# schema.net
KiCad netlist of a schematic drawn in EAGLE
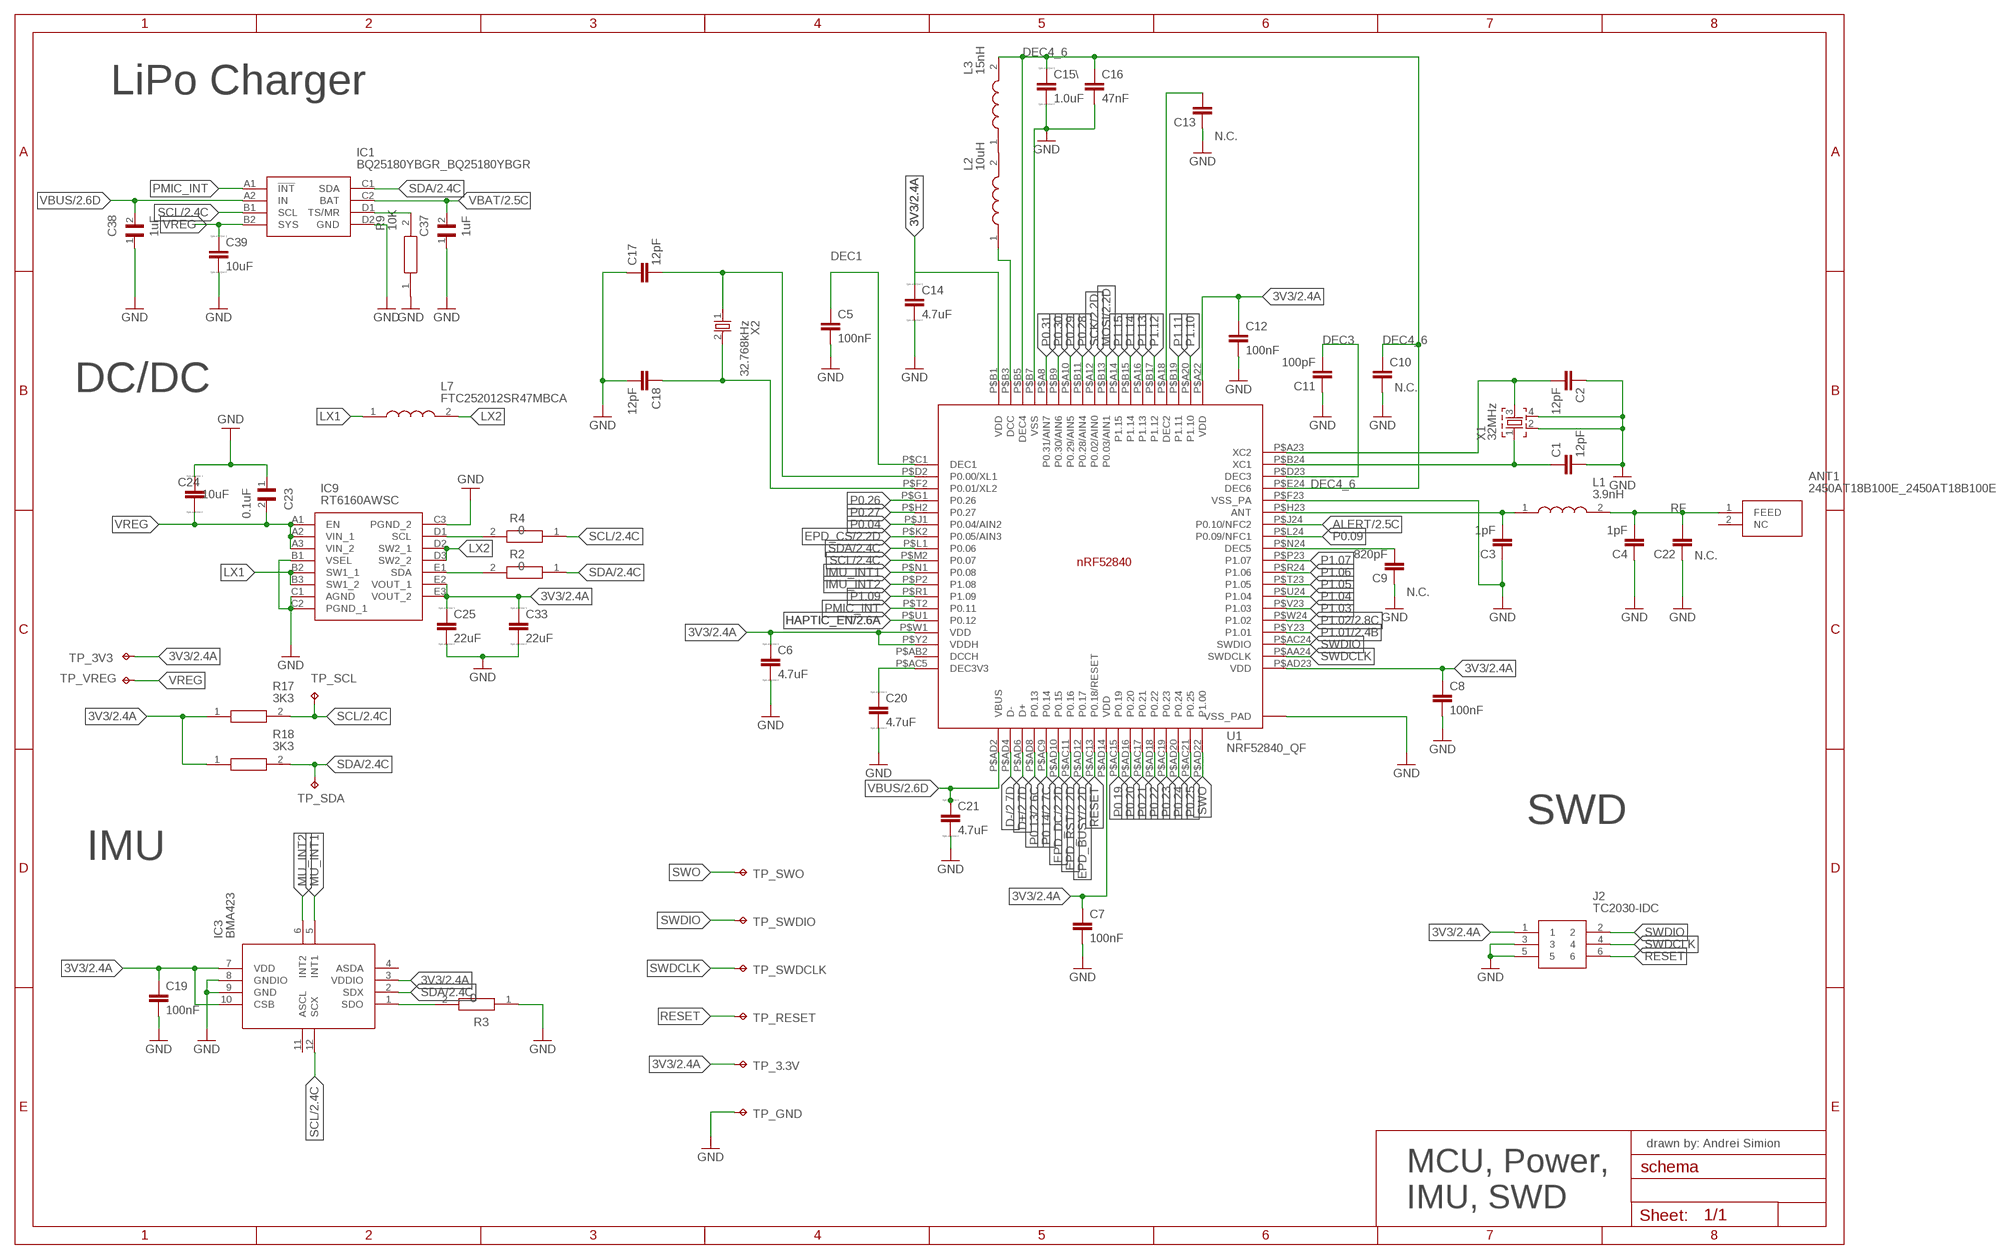
[diagram p0: schematic, sheet 1, part 1 of 2]
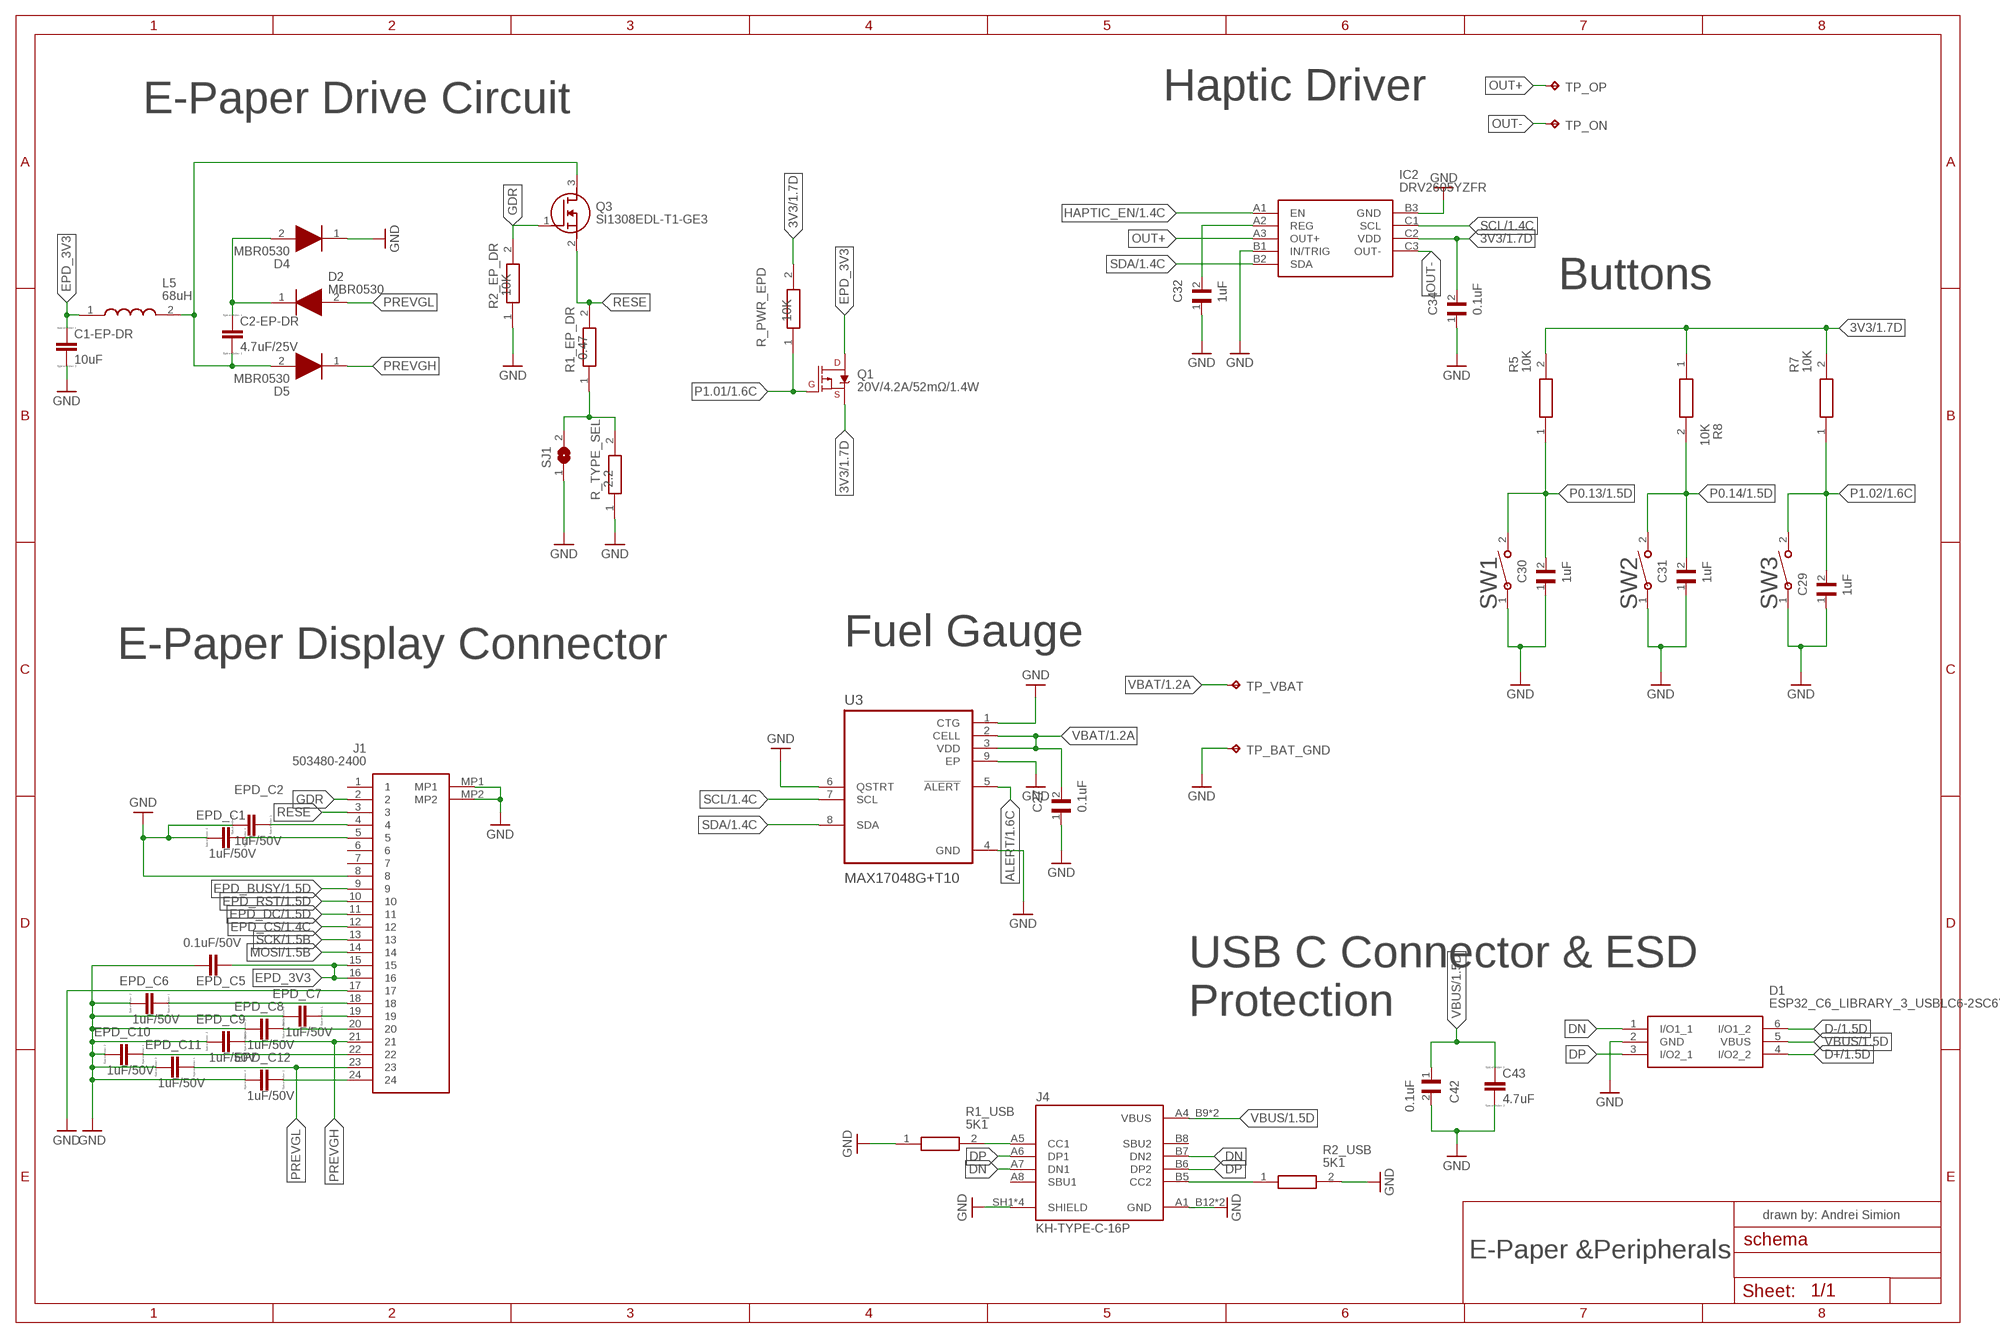
[diagram p1: schematic, sheet 1, part 2 of 2]

(export (version "E")
  (design (tool "Eeschema 10.0.6"))
  (components
    (comp (ref "ANT1")
      (value "2450AT18B100E_2450AT18B100E")
      (footprint "eagle-import:2450AT18B100E_ANTC3216X140N")
      (fields
        (field (name "ARROW_PART_NUMBER") "2450AT18B100E")
        (field (name "MOUSER_PART_NUMBER") "609-2450AT18B100E")
      )
      (libsource (lib "eagle-import") (part "2450AT18B100E_2450AT18B100E"))
    )
    (comp (ref "C1")
      (value "12pF")
      (footprint "eagle-import:NORDIC_NRF_3_RESC0201_L")
      (libsource (lib "eagle-import") (part "NORDIC_NRF_3_CAPACITOR_0201_L"))
    )
    (comp (ref "C1-EP-DR")
      (value "10uF")
      (footprint "eagle-import:ESP32_C6_LIBRARY_1_ESP32_WROVER_EAGLE-LTSPICE_C0402")
      (libsource (lib "eagle-import") (part "ESP32_C6_LIBRARY_1_ESP32_WROVER_EAGLE-LTSPICE_CC0402"))
    )
    (comp (ref "C2")
      (value "12pF")
      (footprint "eagle-import:NORDIC_NRF_3_RESC0201_L")
      (libsource (lib "eagle-import") (part "NORDIC_NRF_3_CAPACITOR_0201_L"))
    )
    (comp (ref "C2-EP-DR")
      (value "4.7uF/25V")
      (footprint "eagle-import:ESP32_C6_LIBRARY_1_ESP32_WROVER_EAGLE-LTSPICE_C0402")
      (libsource (lib "eagle-import") (part "ESP32_C6_LIBRARY_1_ESP32_WROVER_EAGLE-LTSPICE_CC0402"))
    )
    (comp (ref "C3")
      (value "1pF")
      (footprint "eagle-import:NORDIC_NRF_3_RESC0201_L")
      (libsource (lib "eagle-import") (part "NORDIC_NRF_3_CAPACITOR_0201_L"))
    )
    (comp (ref "C4")
      (value "1pF")
      (footprint "eagle-import:NORDIC_NRF_3_RESC0201_L")
      (libsource (lib "eagle-import") (part "NORDIC_NRF_3_CAPACITOR_0201_L"))
    )
    (comp (ref "C5")
      (value "100nF")
      (footprint "eagle-import:NORDIC_NRF_3_RESC0201_L")
      (libsource (lib "eagle-import") (part "NORDIC_NRF_3_CAPACITOR_0201_L"))
    )
    (comp (ref "C6")
      (value "4.7uF")
      (footprint "eagle-import:ESP32_C6_LIBRARY_1_ESP32_WROVER_EAGLE-LTSPICE_C0402")
      (libsource (lib "eagle-import") (part "ESP32_C6_LIBRARY_1_ESP32_WROVER_EAGLE-LTSPICE_CC0402"))
    )
    (comp (ref "C7")
      (value "100nF")
      (footprint "eagle-import:NORDIC_NRF_3_RESC0201_L")
      (libsource (lib "eagle-import") (part "NORDIC_NRF_3_CAPACITOR_0201_L"))
    )
    (comp (ref "C8")
      (value "100nF")
      (footprint "eagle-import:NORDIC_NRF_3_RESC0201_L")
      (libsource (lib "eagle-import") (part "NORDIC_NRF_3_CAPACITOR_0201_L"))
    )
    (comp (ref "C9")
      (value "820pF")
      (footprint "eagle-import:NORDIC_NRF_3_RESC0201_L")
      (libsource (lib "eagle-import") (part "NORDIC_NRF_3_CAPACITOR_0201_L"))
    )
    (comp (ref "C10")
      (value "NORDIC_NRF_3_CAPACITOR_0201_L")
      (footprint "eagle-import:NORDIC_NRF_3_RESC0201_L")
      (libsource (lib "eagle-import") (part "NORDIC_NRF_3_CAPACITOR_0201_L"))
    )
    (comp (ref "C11")
      (value "100pF")
      (footprint "eagle-import:NORDIC_NRF_3_RESC0201_L")
      (libsource (lib "eagle-import") (part "NORDIC_NRF_3_CAPACITOR_0201_L"))
    )
    (comp (ref "C12")
      (value "100nF")
      (footprint "eagle-import:NORDIC_NRF_3_RESC0201_L")
      (libsource (lib "eagle-import") (part "NORDIC_NRF_3_CAPACITOR_0201_L"))
    )
    (comp (ref "C13")
      (value "NORDIC_NRF_3_CAPACITOR_0201_L")
      (footprint "eagle-import:NORDIC_NRF_3_RESC0201_L")
      (libsource (lib "eagle-import") (part "NORDIC_NRF_3_CAPACITOR_0201_L"))
    )
    (comp (ref "C14")
      (value "4.7uF")
      (footprint "eagle-import:ESP32_C6_LIBRARY_1_ESP32_WROVER_EAGLE-LTSPICE_C0402")
      (libsource (lib "eagle-import") (part "ESP32_C6_LIBRARY_1_ESP32_WROVER_EAGLE-LTSPICE_CC0402"))
    )
    (comp (ref "C15\\")
      (value "1.0uF")
      (footprint "eagle-import:ESP32_C6_LIBRARY_1_ESP32_WROVER_EAGLE-LTSPICE_C0402")
      (libsource (lib "eagle-import") (part "ESP32_C6_LIBRARY_1_ESP32_WROVER_EAGLE-LTSPICE_CC0402"))
    )
    (comp (ref "C16")
      (value "47nF")
      (footprint "eagle-import:NORDIC_NRF_3_RESC0201_L")
      (libsource (lib "eagle-import") (part "NORDIC_NRF_3_CAPACITOR_0201_L"))
    )
    (comp (ref "C17")
      (value "12pF")
      (footprint "eagle-import:NORDIC_NRF_3_RESC0201_L")
      (libsource (lib "eagle-import") (part "NORDIC_NRF_3_CAPACITOR_0201_L"))
    )
    (comp (ref "C18")
      (value "12pF")
      (footprint "eagle-import:NORDIC_NRF_3_RESC0201_L")
      (libsource (lib "eagle-import") (part "NORDIC_NRF_3_CAPACITOR_0201_L"))
    )
    (comp (ref "C19")
      (value "100nF")
      (footprint "eagle-import:NORDIC_NRF_3_RESC0201_L")
      (libsource (lib "eagle-import") (part "NORDIC_NRF_3_CAPACITOR_0201_L"))
    )
    (comp (ref "C20")
      (value "4.7uF")
      (footprint "eagle-import:ESP32_C6_LIBRARY_1_ESP32_WROVER_EAGLE-LTSPICE_C0402")
      (libsource (lib "eagle-import") (part "ESP32_C6_LIBRARY_1_ESP32_WROVER_EAGLE-LTSPICE_CC0402"))
    )
    (comp (ref "C21")
      (value "4.7uF")
      (footprint "eagle-import:ESP32_C6_LIBRARY_1_ESP32_WROVER_EAGLE-LTSPICE_C0402")
      (libsource (lib "eagle-import") (part "ESP32_C6_LIBRARY_1_ESP32_WROVER_EAGLE-LTSPICE_CC0402"))
    )
    (comp (ref "C22")
      (value "NORDIC_NRF_3_CAPACITOR_0201_L")
      (footprint "eagle-import:NORDIC_NRF_3_RESC0201_L")
      (libsource (lib "eagle-import") (part "NORDIC_NRF_3_CAPACITOR_0201_L"))
    )
    (comp (ref "C23")
      (value "0.1uF")
      (footprint "eagle-import:GRM011R60J152KE01L_2_CAPC0201X13N")
      (fields (field (name "MF") "Murata") (field (name "MP") "GRM011R60J152KE01L"))
      (libsource (lib "eagle-import") (part "GRM011R60J152KE01L_2_GRM011R60J152KE01L"))
    )
    (comp (ref "C24")
      (value "10uF")
      (footprint "eagle-import:ESP32_C6_LIBRARY_1_ESP32_WROVER_EAGLE-LTSPICE_C0402")
      (libsource (lib "eagle-import") (part "ESP32_C6_LIBRARY_1_ESP32_WROVER_EAGLE-LTSPICE_CC0402"))
    )
    (comp (ref "C25")
      (value "22uF")
      (footprint "eagle-import:ESP32_C6_LIBRARY_1_ESP32_WROVER_EAGLE-LTSPICE_C0402")
      (libsource (lib "eagle-import") (part "ESP32_C6_LIBRARY_1_ESP32_WROVER_EAGLE-LTSPICE_CC0402"))
    )
    (comp (ref "C27")
      (value "0.1uF")
      (footprint "eagle-import:GRM011R60J152KE01L_2_CAPC0201X13N")
      (fields (field (name "MF") "Murata") (field (name "MP") "GRM011R60J152KE01L"))
      (libsource (lib "eagle-import") (part "GRM011R60J152KE01L_2_GRM011R60J152KE01L"))
    )
    (comp (ref "C29")
      (value "1uF")
      (footprint "eagle-import:GRM011R60J152KE01L_2_CAPC0201X13N")
      (fields (field (name "MF") "Murata") (field (name "MP") "GRM011R60J152KE01L"))
      (libsource (lib "eagle-import") (part "GRM011R60J152KE01L_2_GRM011R60J152KE01L"))
    )
    (comp (ref "C30")
      (value "1uF")
      (footprint "eagle-import:GRM011R60J152KE01L_2_CAPC0201X13N")
      (fields (field (name "MF") "Murata") (field (name "MP") "GRM011R60J152KE01L"))
      (libsource (lib "eagle-import") (part "GRM011R60J152KE01L_2_GRM011R60J152KE01L"))
    )
    (comp (ref "C31")
      (value "1uF")
      (footprint "eagle-import:GRM011R60J152KE01L_2_CAPC0201X13N")
      (fields (field (name "MF") "Murata") (field (name "MP") "GRM011R60J152KE01L"))
      (libsource (lib "eagle-import") (part "GRM011R60J152KE01L_2_GRM011R60J152KE01L"))
    )
    (comp (ref "C32")
      (value "1uF")
      (footprint "eagle-import:GRM011R60J152KE01L_2_CAPC0201X13N")
      (fields (field (name "MF") "Murata") (field (name "MP") "GRM011R60J152KE01L"))
      (libsource (lib "eagle-import") (part "GRM011R60J152KE01L_2_GRM011R60J152KE01L"))
    )
    (comp (ref "C33")
      (value "22uF")
      (footprint "eagle-import:ESP32_C6_LIBRARY_1_ESP32_WROVER_EAGLE-LTSPICE_C0402")
      (libsource (lib "eagle-import") (part "ESP32_C6_LIBRARY_1_ESP32_WROVER_EAGLE-LTSPICE_CC0402"))
    )
    (comp (ref "C34")
      (value "0.1uF")
      (footprint "eagle-import:GRM011R60J152KE01L_2_CAPC0201X13N")
      (fields (field (name "MF") "Murata") (field (name "MP") "GRM011R60J152KE01L"))
      (libsource (lib "eagle-import") (part "GRM011R60J152KE01L_2_GRM011R60J152KE01L"))
    )
    (comp (ref "C37")
      (value "1uF")
      (footprint "eagle-import:GRM011R60J152KE01L_2_CAPC0201X13N")
      (fields (field (name "MF") "Murata") (field (name "MP") "GRM011R60J152KE01L"))
      (libsource (lib "eagle-import") (part "GRM011R60J152KE01L_2_GRM011R60J152KE01L"))
    )
    (comp (ref "C38")
      (value "1uF")
      (footprint "eagle-import:GRM011R60J152KE01L_2_CAPC0201X13N")
      (fields (field (name "MF") "Murata") (field (name "MP") "GRM011R60J152KE01L"))
      (libsource (lib "eagle-import") (part "GRM011R60J152KE01L_2_GRM011R60J152KE01L"))
    )
    (comp (ref "C39")
      (value "10uF")
      (footprint "eagle-import:ESP32_C6_LIBRARY_1_ESP32_WROVER_EAGLE-LTSPICE_C0402")
      (libsource (lib "eagle-import") (part "ESP32_C6_LIBRARY_1_ESP32_WROVER_EAGLE-LTSPICE_CC0402"))
    )
    (comp (ref "C42")
      (value "0.1uF")
      (footprint "eagle-import:GRM011R60J152KE01L_2_CAPC0201X13N")
      (fields (field (name "MF") "Murata") (field (name "MP") "GRM011R60J152KE01L"))
      (libsource (lib "eagle-import") (part "GRM011R60J152KE01L_2_GRM011R60J152KE01L"))
    )
    (comp (ref "C43")
      (value "4.7uF")
      (footprint "eagle-import:ESP32_C6_LIBRARY_1_ESP32_WROVER_EAGLE-LTSPICE_C0402")
      (libsource (lib "eagle-import") (part "ESP32_C6_LIBRARY_1_ESP32_WROVER_EAGLE-LTSPICE_CC0402"))
    )
    (comp (ref "D1")
      (value "ESP32_C6_LIBRARY_3_USBLC6-2SC6Y")
      (footprint "eagle-import:ESP32_C6_LIBRARY_3_SOT95P280X145-6N")
      (fields (field (name "MF") "STMicroelectronics") (field (name "MP") "USBLC6-2SC6Y"))
      (libsource (lib "eagle-import") (part "ESP32_C6_LIBRARY_3_USBLC6-2SC6Y"))
    )
    (comp (ref "D2")
      (value "MBR0530")
      (footprint "eagle-import:ESP32_C6_LIBRARY_5_SOD3716X135N")
      (fields (field (name "MF") "ON Semiconductor"))
      (libsource (lib "eagle-import") (part "ESP32_C6_LIBRARY_5_MBR0530"))
    )
    (comp (ref "D4")
      (value "MBR0530")
      (footprint "eagle-import:ESP32_C6_LIBRARY_5_SOD3716X135N")
      (fields (field (name "MF") "ON Semiconductor"))
      (libsource (lib "eagle-import") (part "ESP32_C6_LIBRARY_5_MBR0530"))
    )
    (comp (ref "D5")
      (value "MBR0530")
      (footprint "eagle-import:ESP32_C6_LIBRARY_5_SOD3716X135N")
      (fields (field (name "MF") "ON Semiconductor"))
      (libsource (lib "eagle-import") (part "ESP32_C6_LIBRARY_5_MBR0530"))
    )
    (comp (ref "EPD_C1")
      (value "1uF/50V")
      (footprint "eagle-import:ESP32_C6_LIBRARY_1_ESP32_WROVER_EAGLE-LTSPICE_C0402")
      (libsource (lib "eagle-import") (part "ESP32_C6_LIBRARY_1_ESP32_WROVER_EAGLE-LTSPICE_CC0402"))
    )
    (comp (ref "EPD_C2")
      (value "1uF/50V")
      (footprint "eagle-import:ESP32_C6_LIBRARY_1_ESP32_WROVER_EAGLE-LTSPICE_C0402")
      (libsource (lib "eagle-import") (part "ESP32_C6_LIBRARY_1_ESP32_WROVER_EAGLE-LTSPICE_CC0402"))
    )
    (comp (ref "EPD_C5")
      (value "0.1uF/50V")
      (footprint "eagle-import:NORDIC_NRF_3_RESC0201_L")
      (libsource (lib "eagle-import") (part "NORDIC_NRF_3_CAPACITOR_0201_L"))
    )
    (comp (ref "EPD_C6")
      (value "1uF/50V")
      (footprint "eagle-import:ESP32_C6_LIBRARY_1_ESP32_WROVER_EAGLE-LTSPICE_C0402")
      (libsource (lib "eagle-import") (part "ESP32_C6_LIBRARY_1_ESP32_WROVER_EAGLE-LTSPICE_CC0402"))
    )
    (comp (ref "EPD_C7")
      (value "1uF/50V")
      (footprint "eagle-import:ESP32_C6_LIBRARY_1_ESP32_WROVER_EAGLE-LTSPICE_C0402")
      (libsource (lib "eagle-import") (part "ESP32_C6_LIBRARY_1_ESP32_WROVER_EAGLE-LTSPICE_CC0402"))
    )
    (comp (ref "EPD_C8")
      (value "1uF/50V")
      (footprint "eagle-import:ESP32_C6_LIBRARY_1_ESP32_WROVER_EAGLE-LTSPICE_C0402")
      (libsource (lib "eagle-import") (part "ESP32_C6_LIBRARY_1_ESP32_WROVER_EAGLE-LTSPICE_CC0402"))
    )
    (comp (ref "EPD_C9")
      (value "1uF/50V")
      (footprint "eagle-import:ESP32_C6_LIBRARY_1_ESP32_WROVER_EAGLE-LTSPICE_C0402")
      (libsource (lib "eagle-import") (part "ESP32_C6_LIBRARY_1_ESP32_WROVER_EAGLE-LTSPICE_CC0402"))
    )
    (comp (ref "EPD_C10")
      (value "1uF/50V")
      (footprint "eagle-import:ESP32_C6_LIBRARY_1_ESP32_WROVER_EAGLE-LTSPICE_C0402")
      (libsource (lib "eagle-import") (part "ESP32_C6_LIBRARY_1_ESP32_WROVER_EAGLE-LTSPICE_CC0402"))
    )
    (comp (ref "EPD_C11")
      (value "1uF/50V")
      (footprint "eagle-import:ESP32_C6_LIBRARY_1_ESP32_WROVER_EAGLE-LTSPICE_C0402")
      (libsource (lib "eagle-import") (part "ESP32_C6_LIBRARY_1_ESP32_WROVER_EAGLE-LTSPICE_CC0402"))
    )
    (comp (ref "EPD_C12")
      (value "1uF/50V")
      (footprint "eagle-import:ESP32_C6_LIBRARY_1_ESP32_WROVER_EAGLE-LTSPICE_C0402")
      (libsource (lib "eagle-import") (part "ESP32_C6_LIBRARY_1_ESP32_WROVER_EAGLE-LTSPICE_CC0402"))
    )
    (comp (ref "IC1")
      (value "BQ25180YBGR_BQ25180YBGR")
      (footprint "eagle-import:BQ25180YBGR_BGA8C40P2X4_100X155X50")
      (fields
        (field (name "ARROW_PART_NUMBER") "BQ25180YBGR")
        (field (name "MOUSER_PART_NUMBER") "595-BQ25180YBGR")
      )
      (libsource (lib "eagle-import") (part "BQ25180YBGR_BQ25180YBGR"))
    )
    (comp (ref "IC2")
      (value "DRV2605YZFR")
      (footprint "eagle-import:DRV2605YZFR_BGA9C50P3X3_144X144X62")
      (libsource (lib "eagle-import") (part "DRV2605YZFR_DRV2605YZFR"))
    )
    (comp (ref "IC3")
      (value "BMA423")
      (footprint "eagle-import:BMA423_BMA423")
      (fields (field (name "MOUSER_PART_NUMBER") "262-BMA423"))
      (libsource (lib "eagle-import") (part "BMA423_BMA423"))
    )
    (comp (ref "IC9")
      (value "RT6160AWSC")
      (footprint "eagle-import:RT6160AWSC_BGA15C40P3X5_140X230X60")
      (fields (field (name "MOUSER_PART_NUMBER") "835-RT6160AWSC"))
      (libsource (lib "eagle-import") (part "RT6160AWSC_RT6160AWSC"))
    )
    (comp (ref "J1")
      (value "503480-2400")
      (footprint "eagle-import:503480-2400_5034802400")
      (fields (field (name "MOUSER_PART_NUMBER") "538-503480-2400"))
      (libsource (lib "eagle-import") (part "503480-2400_503480-2400"))
    )
    (comp (ref "J2")
      (value "TC2030-IDC")
      (footprint "eagle-import:TC2030-IDC_TC2030IDC")
      (libsource (lib "eagle-import") (part "TC2030-IDC_TC2030-IDC"))
    )
    (comp (ref "J4")
      (value "KH-TYPE-C-16P")
      (footprint "eagle-import:KH-TYPE-C-16P_KINGHELM_KH-TYPE-C-16P")
      (fields (field (name "MF") "kinghelm"))
      (libsource (lib "eagle-import") (part "KH-TYPE-C-16P_KH-TYPE-C-16P"))
    )
    (comp (ref "L1")
      (value "3.9nH")
      (footprint "eagle-import:MLP2016SR47MT0S1_INDC2016X100N")
      (fields (field (name "MANUFACTURER_PART_NUMBER") "FTC252012SR47MBCA"))
      (libsource (lib "eagle-import") (part "MLP2016SR47MT0S1_FTC252012SR47MBCA"))
    )
    (comp (ref "L2")
      (value "10uH")
      (footprint "eagle-import:MLP2016SR47MT0S1_INDC2016X100N")
      (fields (field (name "MANUFACTURER_PART_NUMBER") "FTC252012SR47MBCA"))
      (libsource (lib "eagle-import") (part "MLP2016SR47MT0S1_FTC252012SR47MBCA"))
    )
    (comp (ref "L3")
      (value "15nH")
      (footprint "eagle-import:MLP2016SR47MT0S1_INDC2016X100N")
      (fields (field (name "MANUFACTURER_PART_NUMBER") "FTC252012SR47MBCA"))
      (libsource (lib "eagle-import") (part "MLP2016SR47MT0S1_FTC252012SR47MBCA"))
    )
    (comp (ref "L5")
      (value "68uH")
      (footprint "eagle-import:MLP2016SR47MT0S1_INDC2016X100N")
      (fields (field (name "MANUFACTURER_PART_NUMBER") "FTC252012SR47MBCA"))
      (libsource (lib "eagle-import") (part "MLP2016SR47MT0S1_FTC252012SR47MBCA"))
    )
    (comp (ref "L7")
      (value "FTC252012SR47MBCA")
      (footprint "eagle-import:MLP2016SR47MT0S1_INDC2016X100N")
      (libsource (lib "eagle-import") (part "MLP2016SR47MT0S1_FTC252012SR47MBCA"))
    )
    (comp (ref "Q1")
      (value "20V/4.2A/52mΩ/1.4W")
      (footprint "eagle-import:ESP32_C6_LIBRARY_4_ESP32_C6_LIBRARY_4_ESP32_C6_LIBRARY_4_ESP32_C6_LIBRARY_4_ESP32_WROVER_SPARKFUN-DISCRETESEMI_SOT23-3")
      (libsource (lib "eagle-import") (part "ESP32_C6_LIBRARY_4_ESP32_WROVER_SPARKFUN-DISCRETESEMI_MOSFET_PCH-DMG2305UX-7"))
    )
    (comp (ref "Q3")
      (value "SI1308EDL-T1-GE3")
      (footprint "eagle-import:ESP32_C6_LIBRARY_6_SOT65P210X110-3N")
      (fields (field (name "MF") "Vishay Siliconix"))
      (libsource (lib "eagle-import") (part "ESP32_C6_LIBRARY_6_SI1308EDL-T1-GE3"))
    )
    (comp (ref "R1_EP_DR")
      (value "0.47")
      (footprint "eagle-import:CPF0201D7K68C1_0201")
      (libsource (lib "eagle-import") (part "CPF0201D7K68C1_CPF0201D7K68C1"))
    )
    (comp (ref "R1_USB")
      (value "5K1")
      (footprint "eagle-import:CPF0201D7K68C1_0201")
      (libsource (lib "eagle-import") (part "CPF0201D7K68C1_CPF0201D7K68C1"))
    )
    (comp (ref "R2")
      (value "0")
      (footprint "eagle-import:CPF0201D7K68C1_0201")
      (libsource (lib "eagle-import") (part "CPF0201D7K68C1_CPF0201D7K68C1"))
    )
    (comp (ref "R2_EP_DR")
      (value "10K")
      (footprint "eagle-import:CPF0201D7K68C1_0201")
      (libsource (lib "eagle-import") (part "CPF0201D7K68C1_CPF0201D7K68C1"))
    )
    (comp (ref "R2_USB")
      (value "5K1")
      (footprint "eagle-import:CPF0201D7K68C1_0201")
      (libsource (lib "eagle-import") (part "CPF0201D7K68C1_CPF0201D7K68C1"))
    )
    (comp (ref "R3")
      (value "0")
      (footprint "eagle-import:CPF0201D7K68C1_0201")
      (libsource (lib "eagle-import") (part "CPF0201D7K68C1_CPF0201D7K68C1"))
    )
    (comp (ref "R4")
      (value "0")
      (footprint "eagle-import:CPF0201D7K68C1_0201")
      (libsource (lib "eagle-import") (part "CPF0201D7K68C1_CPF0201D7K68C1"))
    )
    (comp (ref "R5")
      (value "10K")
      (footprint "eagle-import:CPF0201D7K68C1_0201")
      (libsource (lib "eagle-import") (part "CPF0201D7K68C1_CPF0201D7K68C1"))
    )
    (comp (ref "R7")
      (value "10K")
      (footprint "eagle-import:CPF0201D7K68C1_0201")
      (libsource (lib "eagle-import") (part "CPF0201D7K68C1_CPF0201D7K68C1"))
    )
    (comp (ref "R8")
      (value "10K")
      (footprint "eagle-import:CPF0201D7K68C1_0201")
      (libsource (lib "eagle-import") (part "CPF0201D7K68C1_CPF0201D7K68C1"))
    )
    (comp (ref "R9")
      (value "10K")
      (footprint "eagle-import:CPF0201D7K68C1_0201")
      (libsource (lib "eagle-import") (part "CPF0201D7K68C1_CPF0201D7K68C1"))
    )
    (comp (ref "R17")
      (value "3K3")
      (footprint "eagle-import:CPF0201D7K68C1_0201")
      (libsource (lib "eagle-import") (part "CPF0201D7K68C1_CPF0201D7K68C1"))
    )
    (comp (ref "R18")
      (value "3K3")
      (footprint "eagle-import:CPF0201D7K68C1_0201")
      (libsource (lib "eagle-import") (part "CPF0201D7K68C1_CPF0201D7K68C1"))
    )
    (comp (ref "R_PWR_EPD")
      (value "10K")
      (footprint "eagle-import:CPF0201D7K68C1_0201")
      (libsource (lib "eagle-import") (part "CPF0201D7K68C1_CPF0201D7K68C1"))
    )
    (comp (ref "R_TYPE_SEL")
      (value "2.2")
      (footprint "eagle-import:CPF0201D7K68C1_0201")
      (libsource (lib "eagle-import") (part "CPF0201D7K68C1_CPF0201D7K68C1"))
    )
    (comp (ref "SJ1")
      (value "ESP32_C6_LIBRARY_7_JUMPER_SJ")
      (footprint "eagle-import:ESP32_C6_LIBRARY_7_JUMPER_SJ")
      (libsource (lib "eagle-import") (part "ESP32_C6_LIBRARY_7_JUMPER_SJ"))
    )
    (comp (ref "SW1")
      (value "2025-10-22_07-23-44_LIBRARY_EVP-AKE31ASW_EVP-AKE31A_PAN")
      (footprint "eagle-import:2025-10-22_07-23-44_LIBRARY_SW_EVP-AKE31A_PAN")
      (fields
        (field (name "MANUFACTURER_PART_NUMBER") "EVP-AKE31A")
        (field (name "COPYRIGHT") "Copyright (C) 2025 Ultra Librarian. All rights reserved.")
      )
      (libsource (lib "eagle-import") (part "2025-10-22_07-23-44_LIBRARY_EVP-AKE31ASW_EVP-AKE31A_PAN"))
    )
    (comp (ref "SW2")
      (value "2025-10-22_07-23-44_LIBRARY_EVP-AKE31ASW_EVP-AKE31A_PAN")
      (footprint "eagle-import:2025-10-22_07-23-44_LIBRARY_SW_EVP-AKE31A_PAN")
      (fields
        (field (name "MANUFACTURER_PART_NUMBER") "EVP-AKE31A")
        (field (name "COPYRIGHT") "Copyright (C) 2025 Ultra Librarian. All rights reserved.")
      )
      (libsource (lib "eagle-import") (part "2025-10-22_07-23-44_LIBRARY_EVP-AKE31ASW_EVP-AKE31A_PAN"))
    )
    (comp (ref "SW3")
      (value "2025-10-22_07-23-44_LIBRARY_EVP-AKE31ASW_EVP-AKE31A_PAN")
      (footprint "eagle-import:2025-10-22_07-23-44_LIBRARY_SW_EVP-AKE31A_PAN")
      (fields
        (field (name "MANUFACTURER_PART_NUMBER") "EVP-AKE31A")
        (field (name "COPYRIGHT") "Copyright (C) 2025 Ultra Librarian. All rights reserved.")
      )
      (libsource (lib "eagle-import") (part "2025-10-22_07-23-44_LIBRARY_EVP-AKE31ASW_EVP-AKE31A_PAN"))
    )
    (comp (ref "TP_3.3V")
      (value "HECTOR_WATCH_1_TPTP20R")
      (footprint "eagle-import:HECTOR_WATCH_1_TP20R")
      (libsource (lib "eagle-import") (part "HECTOR_WATCH_1_TPTP20R"))
    )
    (comp (ref "TP_3V3")
      (value "HECTOR_WATCH_1_TPTP20R")
      (footprint "eagle-import:HECTOR_WATCH_1_TP20R")
      (libsource (lib "eagle-import") (part "HECTOR_WATCH_1_TPTP20R"))
    )
    (comp (ref "TP_BAT_GND")
      (value "HECTOR_WATCH_1_TPTP20R")
      (footprint "eagle-import:HECTOR_WATCH_1_TP20R")
      (libsource (lib "eagle-import") (part "HECTOR_WATCH_1_TPTP20R"))
    )
    (comp (ref "TP_GND")
      (value "HECTOR_WATCH_1_TPTP20R")
      (footprint "eagle-import:HECTOR_WATCH_1_TP20R")
      (libsource (lib "eagle-import") (part "HECTOR_WATCH_1_TPTP20R"))
    )
    (comp (ref "TP_ON")
      (value "HECTOR_WATCH_1_TPTP20R")
      (footprint "eagle-import:HECTOR_WATCH_1_TP20R")
      (libsource (lib "eagle-import") (part "HECTOR_WATCH_1_TPTP20R"))
    )
    (comp (ref "TP_OP")
      (value "HECTOR_WATCH_1_TPTP20R")
      (footprint "eagle-import:HECTOR_WATCH_1_TP20R")
      (libsource (lib "eagle-import") (part "HECTOR_WATCH_1_TPTP20R"))
    )
    (comp (ref "TP_RESET")
      (value "HECTOR_WATCH_1_TPTP20R")
      (footprint "eagle-import:HECTOR_WATCH_1_TP20R")
      (libsource (lib "eagle-import") (part "HECTOR_WATCH_1_TPTP20R"))
    )
    (comp (ref "TP_SCL")
      (value "HECTOR_WATCH_1_TPTP20R")
      (footprint "eagle-import:HECTOR_WATCH_1_TP20R")
      (libsource (lib "eagle-import") (part "HECTOR_WATCH_1_TPTP20R"))
    )
    (comp (ref "TP_SDA")
      (value "HECTOR_WATCH_1_TPTP20R")
      (footprint "eagle-import:HECTOR_WATCH_1_TP20R")
      (libsource (lib "eagle-import") (part "HECTOR_WATCH_1_TPTP20R"))
    )
    (comp (ref "TP_SWDCLK")
      (value "HECTOR_WATCH_1_TPTP20R")
      (footprint "eagle-import:HECTOR_WATCH_1_TP20R")
      (libsource (lib "eagle-import") (part "HECTOR_WATCH_1_TPTP20R"))
    )
    (comp (ref "TP_SWDIO")
      (value "HECTOR_WATCH_1_TPTP20R")
      (footprint "eagle-import:HECTOR_WATCH_1_TP20R")
      (libsource (lib "eagle-import") (part "HECTOR_WATCH_1_TPTP20R"))
    )
    (comp (ref "TP_SWO")
      (value "HECTOR_WATCH_1_TPTP20R")
      (footprint "eagle-import:HECTOR_WATCH_1_TP20R")
      (libsource (lib "eagle-import") (part "HECTOR_WATCH_1_TPTP20R"))
    )
    (comp (ref "TP_VBAT")
      (value "HECTOR_WATCH_1_TPTP20R")
      (footprint "eagle-import:HECTOR_WATCH_1_TP20R")
      (libsource (lib "eagle-import") (part "HECTOR_WATCH_1_TPTP20R"))
    )
    (comp (ref "TP_VREG")
      (value "HECTOR_WATCH_1_TPTP20R")
      (footprint "eagle-import:HECTOR_WATCH_1_TP20R")
      (libsource (lib "eagle-import") (part "HECTOR_WATCH_1_TPTP20R"))
    )
    (comp (ref "U1")
      (value "NRF52840_QF")
      (footprint "eagle-import:NORDIC_NRF_4_AQFN50P700X700X85_HS-74N")
      (libsource (lib "eagle-import") (part "NORDIC_NRF_4_NRF52840_QF"))
    )
    (comp (ref "U3")
      (value "MAX17048G+T10")
      (footprint "eagle-import:ESP32_C6_LIBRARY_SON50P200X200X80-9N")
      (fields (field (name "MF") "Analog Devices"))
      (libsource (lib "eagle-import") (part "ESP32_C6_LIBRARY_MAX17048G+T10"))
    )
    (comp (ref "X1")
      (value "32MHz")
      (footprint "eagle-import:NORDIC_NRF_BT-XTAL_2016_N")
      (libsource (lib "eagle-import") (part "NORDIC_NRF_XTAL_32MHZ"))
    )
    (comp (ref "X2")
      (value "32.768kHz")
      (footprint "eagle-import:NORDIC_NRF_1_XTAL_3215_N")
      (libsource (lib "eagle-import") (part "NORDIC_NRF_1_XTAL_32KHZ"))
    )
  )
  (nets
    (net (code "1") (name "3V3{slash}1.7D") (class "Default")
      (node (ref "C34") (pin "2") (pinfunction "2_2") (pintype "passive"))
      (node (ref "IC2") (pin "C2") (pinfunction "VDD_C2") (pintype "bidirectional"))
      (node (ref "Q1") (pin "2") (pinfunction "S_2") (pintype "bidirectional"))
      (node (ref "R5") (pin "2") (pinfunction "2_2") (pintype "bidirectional"))
      (node (ref "R7") (pin "2") (pinfunction "2_2") (pintype "bidirectional"))
      (node (ref "R8") (pin "1") (pinfunction "1_1") (pintype "bidirectional"))
      (node (ref "R_PWR_EPD") (pin "2") (pinfunction "2_2") (pintype "bidirectional"))
    )
    (net (code "2") (name "3V3{slash}2.4A") (class "Default")
      (node (ref "C12") (pin "1") (pinfunction "1_1") (pintype "passive"))
      (node (ref "C14") (pin "1") (pinfunction "1_1") (pintype "passive"))
      (node (ref "C19") (pin "1") (pinfunction "1_1") (pintype "passive"))
      (node (ref "C25") (pin "1") (pinfunction "1_1") (pintype "passive"))
      (node (ref "C33") (pin "1") (pinfunction "1_1") (pintype "passive"))
      (node (ref "C6") (pin "1") (pinfunction "1_1") (pintype "passive"))
      (node (ref "C7") (pin "1") (pinfunction "1_1") (pintype "passive"))
      (node (ref "C8") (pin "1") (pinfunction "1_1") (pintype "passive"))
      (node (ref "IC3") (pin "10") (pinfunction "CSB_10") (pintype "bidirectional"))
      (node (ref "IC3") (pin "3") (pinfunction "VDDIO_3") (pintype "bidirectional"))
      (node (ref "IC3") (pin "7") (pinfunction "VDD_7") (pintype "bidirectional"))
      (node (ref "IC9") (pin "E2") (pinfunction "VOUT_1_E2") (pintype "bidirectional"))
      (node (ref "IC9") (pin "E3") (pinfunction "VOUT_2_E3") (pintype "bidirectional"))
      (node (ref "J2") (pin "1") (pinfunction "1_1") (pintype "bidirectional"))
      (node (ref "R17") (pin "1") (pinfunction "1_1") (pintype "bidirectional"))
      (node (ref "R18") (pin "1") (pinfunction "1_1") (pintype "bidirectional"))
      (node (ref "TP_3.3V") (pin "TP") (pinfunction "TP_TP") (pintype "input"))
      (node (ref "TP_3V3") (pin "TP") (pinfunction "TP_TP") (pintype "input"))
      (node (ref "U1") (pin "P$A22") (pinfunction "VDD_P$A22") (pintype "power_in"))
      (node (ref "U1") (pin "P$AD14") (pinfunction "VDD_P$AD14") (pintype "power_in"))
      (node (ref "U1") (pin "P$AD23") (pinfunction "VDD_P$AD23") (pintype "power_in"))
      (node (ref "U1") (pin "P$B1") (pinfunction "VDD_P$B1") (pintype "power_in"))
      (node (ref "U1") (pin "P$W1") (pinfunction "VDD_P$W1") (pintype "power_in"))
      (node (ref "U1") (pin "P$Y2") (pinfunction "VDDH_P$Y2") (pintype "power_in"))
    )
    (net (code "3") (name "ALERT{slash}1.6C") (class "Default")
      (node (ref "U3") (pin "5") (pinfunction "~{ALERT}_5") (pintype "output"))
    )
    (net (code "4") (name "ALERT{slash}2.5C") (class "Default")
      (node (ref "U1") (pin "P$J24") (pinfunction "P0.10/NFC2_P$J24") (pintype "bidirectional"))
    )
    (net (code "5") (name "D+{slash}1.5D") (class "Default")
      (node (ref "D1") (pin "4") (pinfunction "I/O2_2_4") (pintype "bidirectional"))
    )
    (net (code "6") (name "D+{slash}2.7D") (class "Default")
      (node (ref "U1") (pin "P$AD6") (pinfunction "D+_P$AD6") (pintype "bidirectional"))
    )
    (net (code "7") (name "D-{slash}1.5D") (class "Default")
      (node (ref "D1") (pin "6") (pinfunction "I/O1_2_6") (pintype "bidirectional"))
    )
    (net (code "8") (name "D-{slash}2.7D") (class "Default")
      (node (ref "U1") (pin "P$AD4") (pinfunction "D-_P$AD4") (pintype "bidirectional"))
    )
    (net (code "9") (name "DN") (class "Default")
      (node (ref "D1") (pin "1") (pinfunction "I/O1_1_1") (pintype "bidirectional"))
      (node (ref "J4") (pin "A7") (pinfunction "DN1_A7") (pintype "bidirectional"))
      (node (ref "J4") (pin "B7") (pinfunction "DN2_B7") (pintype "bidirectional"))
    )
    (net (code "10") (name "DP") (class "Default")
      (node (ref "D1") (pin "3") (pinfunction "I/O2_1_3") (pintype "bidirectional"))
      (node (ref "J4") (pin "A6") (pinfunction "DP1_A6") (pintype "bidirectional"))
      (node (ref "J4") (pin "B6") (pinfunction "DP2_B6") (pintype "bidirectional"))
    )
    (net (code "11") (name "EPD_3V3") (class "Default")
      (node (ref "C1-EP-DR") (pin "1") (pinfunction "1_1") (pintype "passive"))
      (node (ref "EPD_C5") (pin "1") (pinfunction "1_1") (pintype "passive"))
      (node (ref "J1") (pin "15") (pinfunction "15_15") (pintype "bidirectional"))
      (node (ref "J1") (pin "16") (pinfunction "16_16") (pintype "bidirectional"))
      (node (ref "L5") (pin "1") (pinfunction "1_1") (pintype "bidirectional"))
      (node (ref "Q1") (pin "3") (pinfunction "D_3") (pintype "bidirectional"))
    )
    (net (code "12") (name "EPD_BUSY{slash}1.5D") (class "Default")
      (node (ref "J1") (pin "9") (pinfunction "9_9") (pintype "bidirectional"))
    )
    (net (code "13") (name "EPD_BUSY{slash}2.2D") (class "Default")
      (node (ref "U1") (pin "P$AD12") (pinfunction "P0.17_P$AD12") (pintype "bidirectional"))
    )
    (net (code "14") (name "EPD_CS{slash}1.4C") (class "Default")
      (node (ref "J1") (pin "12") (pinfunction "12_12") (pintype "bidirectional"))
    )
    (net (code "15") (name "EPD_CS{slash}2.2D") (class "Default")
      (node (ref "U1") (pin "P$K2") (pinfunction "P0.05/AIN3_P$K2") (pintype "bidirectional"))
    )
    (net (code "16") (name "EPD_DC{slash}1.5D") (class "Default")
      (node (ref "J1") (pin "11") (pinfunction "11_11") (pintype "bidirectional"))
    )
    (net (code "17") (name "EPD_DC{slash}2.2D") (class "Default")
      (node (ref "U1") (pin "P$AD10") (pinfunction "P0.15_P$AD10") (pintype "bidirectional"))
    )
    (net (code "18") (name "EPD_RST{slash}1.5D") (class "Default")
      (node (ref "J1") (pin "10") (pinfunction "10_10") (pintype "bidirectional"))
    )
    (net (code "19") (name "EPD_RST{slash}2.2D") (class "Default")
      (node (ref "U1") (pin "P$AC11") (pinfunction "P0.16_P$AC11") (pintype "bidirectional"))
    )
    (net (code "20") (name "GDR") (class "Default")
      (node (ref "J1") (pin "2") (pinfunction "2_2") (pintype "bidirectional"))
      (node (ref "Q3") (pin "1") (pinfunction "G_1") (pintype "bidirectional"))
      (node (ref "R2_EP_DR") (pin "2") (pinfunction "2_2") (pintype "bidirectional"))
    )
    (net (code "21") (name "GND") (class "Default")
      (node (ref "C1") (pin "2") (pinfunction "2_2") (pintype "passive"))
      (node (ref "C1-EP-DR") (pin "2") (pinfunction "2_2") (pintype "passive"))
      (node (ref "C10") (pin "2") (pinfunction "2_2") (pintype "passive"))
      (node (ref "C11") (pin "1") (pinfunction "1_1") (pintype "passive"))
      (node (ref "C12") (pin "2") (pinfunction "2_2") (pintype "passive"))
      (node (ref "C13") (pin "1") (pinfunction "1_1") (pintype "passive"))
      (node (ref "C14") (pin "2") (pinfunction "2_2") (pintype "passive"))
      (node (ref "C15\\") (pin "2") (pinfunction "2_2") (pintype "passive"))
      (node (ref "C16") (pin "2") (pinfunction "2_2") (pintype "passive"))
      (node (ref "C17") (pin "1") (pinfunction "1_1") (pintype "passive"))
      (node (ref "C18") (pin "2") (pinfunction "2_2") (pintype "passive"))
      (node (ref "C19") (pin "2") (pinfunction "2_2") (pintype "passive"))
      (node (ref "C2") (pin "1") (pinfunction "1_1") (pintype "passive"))
      (node (ref "C20") (pin "2") (pinfunction "2_2") (pintype "passive"))
      (node (ref "C21") (pin "2") (pinfunction "2_2") (pintype "passive"))
      (node (ref "C22") (pin "1") (pinfunction "1_1") (pintype "passive"))
      (node (ref "C23") (pin "1") (pinfunction "1_1") (pintype "passive"))
      (node (ref "C24") (pin "1") (pinfunction "1_1") (pintype "passive"))
      (node (ref "C25") (pin "2") (pinfunction "2_2") (pintype "passive"))
      (node (ref "C27") (pin "1") (pinfunction "1_1") (pintype "passive"))
      (node (ref "C29") (pin "1") (pinfunction "1_1") (pintype "passive"))
      (node (ref "C3") (pin "1") (pinfunction "1_1") (pintype "passive"))
      (node (ref "C30") (pin "1") (pinfunction "1_1") (pintype "passive"))
      (node (ref "C31") (pin "1") (pinfunction "1_1") (pintype "passive"))
      (node (ref "C32") (pin "1") (pinfunction "1_1") (pintype "passive"))
      (node (ref "C33") (pin "2") (pinfunction "2_2") (pintype "passive"))
      (node (ref "C34") (pin "1") (pinfunction "1_1") (pintype "passive"))
      (node (ref "C37") (pin "1") (pinfunction "1_1") (pintype "passive"))
      (node (ref "C38") (pin "1") (pinfunction "1_1") (pintype "passive"))
      (node (ref "C39") (pin "2") (pinfunction "2_2") (pintype "passive"))
      (node (ref "C4") (pin "1") (pinfunction "1_1") (pintype "passive"))
      (node (ref "C42") (pin "2") (pinfunction "2_2") (pintype "passive"))
      (node (ref "C43") (pin "2") (pinfunction "2_2") (pintype "passive"))
      (node (ref "C5") (pin "2") (pinfunction "2_2") (pintype "passive"))
      (node (ref "C6") (pin "2") (pinfunction "2_2") (pintype "passive"))
      (node (ref "C7") (pin "2") (pinfunction "2_2") (pintype "passive"))
      (node (ref "C8") (pin "2") (pinfunction "2_2") (pintype "passive"))
      (node (ref "C9") (pin "1") (pinfunction "1_1") (pintype "passive"))
      (node (ref "D1") (pin "2") (pinfunction "GND_2") (pintype "bidirectional"))
      (node (ref "D4") (pin "1") (pinfunction "K_1") (pintype "bidirectional"))
      (node (ref "EPD_C1") (pin "2") (pinfunction "2_2") (pintype "passive"))
      (node (ref "EPD_C10") (pin "2") (pinfunction "2_2") (pintype "passive"))
      (node (ref "EPD_C11") (pin "2") (pinfunction "2_2") (pintype "passive"))
      (node (ref "EPD_C12") (pin "2") (pinfunction "2_2") (pintype "passive"))
      (node (ref "EPD_C2") (pin "2") (pinfunction "2_2") (pintype "passive"))
      (node (ref "EPD_C5") (pin "2") (pinfunction "2_2") (pintype "passive"))
      (node (ref "EPD_C6") (pin "2") (pinfunction "2_2") (pintype "passive"))
      (node (ref "EPD_C7") (pin "2") (pinfunction "2_2") (pintype "passive"))
      (node (ref "EPD_C8") (pin "2") (pinfunction "2_2") (pintype "passive"))
      (node (ref "EPD_C9") (pin "2") (pinfunction "2_2") (pintype "passive"))
      (node (ref "IC1") (pin "D2") (pinfunction "GND_D2") (pintype "bidirectional"))
      (node (ref "IC2") (pin "B1") (pinfunction "IN/TRIG_B1") (pintype "bidirectional"))
      (node (ref "IC2") (pin "B3") (pinfunction "GND_B3") (pintype "bidirectional"))
      (node (ref "IC3") (pin "8") (pinfunction "GNDIO_8") (pintype "bidirectional"))
      (node (ref "IC3") (pin "9") (pinfunction "GND_9") (pintype "bidirectional"))
      (node (ref "IC9") (pin "B1") (pinfunction "VSEL_B1") (pintype "bidirectional"))
      (node (ref "IC9") (pin "C1") (pinfunction "AGND_C1") (pintype "bidirectional"))
      (node (ref "IC9") (pin "C2") (pinfunction "PGND_1_C2") (pintype "bidirectional"))
      (node (ref "IC9") (pin "C3") (pinfunction "PGND_2_C3") (pintype "bidirectional"))
      (node (ref "J1") (pin "17") (pinfunction "17_17") (pintype "bidirectional"))
      (node (ref "J1") (pin "8") (pinfunction "8_8") (pintype "bidirectional"))
      (node (ref "J1") (pin "MP1") (pinfunction "MP1_MP1") (pintype "bidirectional"))
      (node (ref "J1") (pin "MP2") (pinfunction "MP2_MP2") (pintype "bidirectional"))
      (node (ref "J2") (pin "3") (pinfunction "3_3") (pintype "bidirectional"))
      (node (ref "J2") (pin "5") (pinfunction "5_5") (pintype "bidirectional"))
      (node (ref "J4") (pin "A12_B1") (pinfunction "GND_A12_B1") (pintype "power_in"))
      (node (ref "J4") (pin "A1_B12") (pinfunction "GND_A1_B12") (pintype "power_in"))
      (node (ref "J4") (pin "SH1") (pinfunction "SHIELD_SH1") (pintype "passive"))
      (node (ref "J4") (pin "SH2") (pinfunction "SHIELD_SH2") (pintype "passive"))
      (node (ref "J4") (pin "SH3") (pinfunction "SHIELD_SH3") (pintype "passive"))
      (node (ref "J4") (pin "SH4") (pinfunction "SHIELD_SH4") (pintype "passive"))
      (node (ref "R1_USB") (pin "1") (pinfunction "1_1") (pintype "bidirectional"))
      (node (ref "R2_EP_DR") (pin "1") (pinfunction "1_1") (pintype "bidirectional"))
      (node (ref "R2_USB") (pin "2") (pinfunction "2_2") (pintype "bidirectional"))
      (node (ref "R3") (pin "1") (pinfunction "1_1") (pintype "bidirectional"))
      (node (ref "R9") (pin "1") (pinfunction "1_1") (pintype "bidirectional"))
      (node (ref "R_TYPE_SEL") (pin "1") (pinfunction "1_1") (pintype "bidirectional"))
      (node (ref "SJ1") (pin "1") (pinfunction "1_1") (pintype "passive"))
      (node (ref "SW1") (pin "1") (pinfunction "1_1") (pintype "passive"))
      (node (ref "SW2") (pin "1") (pinfunction "1_1") (pintype "passive"))
      (node (ref "SW3") (pin "1") (pinfunction "1_1") (pintype "passive"))
      (node (ref "TP_BAT_GND") (pin "TP") (pinfunction "TP_TP") (pintype "input"))
      (node (ref "TP_GND") (pin "TP") (pinfunction "TP_TP") (pintype "input"))
      (node (ref "U1") (pin "P$74") (pinfunction "VSS_PAD_P$74") (pintype "bidirectional"))
      (node (ref "U1") (pin "P$75") (pinfunction "VSS_PAD_P$75") (pintype "bidirectional"))
      (node (ref "U1") (pin "P$76") (pinfunction "VSS_PAD_P$76") (pintype "bidirectional"))
      (node (ref "U1") (pin "P$77") (pinfunction "VSS_PAD_P$77") (pintype "bidirectional"))
      (node (ref "U1") (pin "P$78") (pinfunction "VSS_PAD_P$78") (pintype "bidirectional"))
      (node (ref "U1") (pin "P$79") (pinfunction "VSS_PAD_P$79") (pintype "bidirectional"))
      (node (ref "U1") (pin "P$80") (pinfunction "VSS_PAD_P$80") (pintype "bidirectional"))
      (node (ref "U1") (pin "P$81") (pinfunction "VSS_PAD_P$81") (pintype "bidirectional"))
      (node (ref "U1") (pin "P$82") (pinfunction "VSS_PAD_P$82") (pintype "bidirectional"))
      (node (ref "U1") (pin "P$83") (pinfunction "VSS_PAD_P$83") (pintype "bidirectional"))
      (node (ref "U1") (pin "P$84") (pinfunction "VSS_PAD_P$84") (pintype "bidirectional"))
      (node (ref "U1") (pin "P$85") (pinfunction "VSS_PAD_P$85") (pintype "bidirectional"))
      (node (ref "U1") (pin "P$86") (pinfunction "VSS_PAD_P$86") (pintype "bidirectional"))
      (node (ref "U1") (pin "P$87") (pinfunction "VSS_PAD_P$87") (pintype "bidirectional"))
      (node (ref "U1") (pin "P$88") (pinfunction "VSS_PAD_P$88") (pintype "bidirectional"))
      (node (ref "U1") (pin "P$89") (pinfunction "VSS_PAD_P$89") (pintype "bidirectional"))
      (node (ref "U1") (pin "P$90") (pinfunction "VSS_PAD_P$90") (pintype "bidirectional"))
      (node (ref "U1") (pin "P$B7") (pinfunction "VSS_P$B7") (pintype "power_in"))
      (node (ref "U1") (pin "P$F23") (pinfunction "VSS_PA_P$F23") (pintype "bidirectional"))
      (node (ref "U3") (pin "1") (pinfunction "CTG_1") (pintype "power_in"))
      (node (ref "U3") (pin "4") (pinfunction "GND_4") (pintype "power_in"))
      (node (ref "U3") (pin "6") (pinfunction "QSTRT_6") (pintype "input"))
      (node (ref "U3") (pin "9") (pinfunction "EP_9") (pintype "power_in"))
      (node (ref "X1") (pin "2") (pinfunction "2_2") (pintype "passive"))
      (node (ref "X1") (pin "4") (pinfunction "4_4") (pintype "passive"))
    )
    (net (code "22") (name "HAPTIC_EN{slash}1.4C") (class "Default")
      (node (ref "IC2") (pin "A1") (pinfunction "EN_A1") (pintype "bidirectional"))
    )
    (net (code "23") (name "HAPTIC_EN{slash}2.6A") (class "Default")
      (node (ref "U1") (pin "P$U1") (pinfunction "P0.12_P$U1") (pintype "bidirectional"))
    )
    (net (code "24") (name "IMU_INT1") (class "Default")
      (node (ref "U1") (pin "P$N1") (pinfunction "P0.08_P$N1") (pintype "bidirectional"))
    )
    (net (code "25") (name "IMU_INT2") (class "Default")
      (node (ref "U1") (pin "P$P2") (pinfunction "P1.08_P$P2") (pintype "bidirectional"))
    )
    (net (code "26") (name "LX1") (class "Default")
      (node (ref "IC9") (pin "B2") (pinfunction "SW1_1_B2") (pintype "bidirectional"))
      (node (ref "IC9") (pin "B3") (pinfunction "SW1_2_B3") (pintype "bidirectional"))
      (node (ref "L7") (pin "1") (pinfunction "1_1") (pintype "bidirectional"))
    )
    (net (code "27") (name "LX2") (class "Default")
      (node (ref "IC9") (pin "D2") (pinfunction "SW2_1_D2") (pintype "bidirectional"))
      (node (ref "IC9") (pin "D3") (pinfunction "SW2_2_D3") (pintype "bidirectional"))
      (node (ref "L7") (pin "2") (pinfunction "2_2") (pintype "bidirectional"))
    )
    (net (code "28") (name "MOSI{slash}1.5B") (class "Default")
      (node (ref "J1") (pin "14") (pinfunction "14_14") (pintype "bidirectional"))
    )
    (net (code "29") (name "MOSI{slash}2.2D") (class "Default")
      (node (ref "U1") (pin "P$B13") (pinfunction "P0.03/AIN1_P$B13") (pintype "bidirectional"))
    )
    (net (code "30") (name "MU_INT1") (class "Default")
      (node (ref "IC3") (pin "5") (pinfunction "INT1_5") (pintype "bidirectional"))
    )
    (net (code "31") (name "MU_INT2") (class "Default")
      (node (ref "IC3") (pin "6") (pinfunction "INT2_6") (pintype "bidirectional"))
    )
    (net (code "32") (name "Net-(ANT1-FEED)") (class "Default")
      (node (ref "ANT1") (pin "1") (pinfunction "FEED_1") (pintype "input"))
      (node (ref "C22") (pin "2") (pinfunction "2_2") (pintype "passive"))
      (node (ref "C4") (pin "2") (pinfunction "2_2") (pintype "passive"))
      (node (ref "L1") (pin "2") (pinfunction "2_2") (pintype "bidirectional"))
    )
    (net (code "33") (name "Net-(D2-K)") (class "Default")
      (node (ref "C2-EP-DR") (pin "1") (pinfunction "1_1") (pintype "passive"))
      (node (ref "D2") (pin "1") (pinfunction "K_1") (pintype "bidirectional"))
      (node (ref "D4") (pin "2") (pinfunction "A_2") (pintype "bidirectional"))
    )
    (net (code "34") (name "Net-(D5-A)") (class "Default")
      (node (ref "C2-EP-DR") (pin "2") (pinfunction "2_2") (pintype "passive"))
      (node (ref "D5") (pin "2") (pinfunction "A_2") (pintype "bidirectional"))
      (node (ref "L5") (pin "2") (pinfunction "2_2") (pintype "bidirectional"))
      (node (ref "Q3") (pin "3") (pinfunction "D_3") (pintype "bidirectional"))
    )
    (net (code "35") (name "Net-(EPD_C1-Pad1)") (class "Default")
      (node (ref "EPD_C1") (pin "1") (pinfunction "1_1") (pintype "passive"))
      (node (ref "J1") (pin "5") (pinfunction "5_5") (pintype "bidirectional"))
    )
    (net (code "36") (name "Net-(EPD_C2-Pad1)") (class "Default")
      (node (ref "EPD_C2") (pin "1") (pinfunction "1_1") (pintype "passive"))
      (node (ref "J1") (pin "4") (pinfunction "4_4") (pintype "bidirectional"))
    )
    (net (code "37") (name "Net-(EPD_C6-Pad1)") (class "Default")
      (node (ref "EPD_C6") (pin "1") (pinfunction "1_1") (pintype "passive"))
      (node (ref "J1") (pin "18") (pinfunction "18_18") (pintype "bidirectional"))
    )
    (net (code "38") (name "Net-(EPD_C7-Pad1)") (class "Default")
      (node (ref "EPD_C7") (pin "1") (pinfunction "1_1") (pintype "passive"))
      (node (ref "J1") (pin "19") (pinfunction "19_19") (pintype "bidirectional"))
    )
    (net (code "39") (name "Net-(EPD_C8-Pad1)") (class "Default")
      (node (ref "EPD_C8") (pin "1") (pinfunction "1_1") (pintype "passive"))
      (node (ref "J1") (pin "20") (pinfunction "20_20") (pintype "bidirectional"))
    )
    (net (code "40") (name "Net-(EPD_C10-Pad1)") (class "Default")
      (node (ref "EPD_C10") (pin "1") (pinfunction "1_1") (pintype "passive"))
      (node (ref "J1") (pin "22") (pinfunction "22_22") (pintype "bidirectional"))
    )
    (net (code "41") (name "Net-(EPD_C12-Pad1)") (class "Default")
      (node (ref "EPD_C12") (pin "1") (pinfunction "1_1") (pintype "passive"))
      (node (ref "J1") (pin "24") (pinfunction "24_24") (pintype "bidirectional"))
    )
    (net (code "42") (name "Net-(IC1-TS{slash}MR)") (class "Default")
      (node (ref "IC1") (pin "D1") (pinfunction "TS/MR_D1") (pintype "bidirectional"))
      (node (ref "R9") (pin "2") (pinfunction "2_2") (pintype "bidirectional"))
    )
    (net (code "43") (name "Net-(IC2-REG)") (class "Default")
      (node (ref "C32") (pin "2") (pinfunction "2_2") (pintype "passive"))
      (node (ref "IC2") (pin "A2") (pinfunction "REG_A2") (pintype "bidirectional"))
    )
    (net (code "44") (name "Net-(IC3-SDO)") (class "Default")
      (node (ref "IC3") (pin "1") (pinfunction "SDO_1") (pintype "bidirectional"))
      (node (ref "R3") (pin "2") (pinfunction "2_2") (pintype "bidirectional"))
    )
    (net (code "45") (name "Net-(IC9-SCL)") (class "Default")
      (node (ref "IC9") (pin "D1") (pinfunction "SCL_D1") (pintype "bidirectional"))
      (node (ref "R4") (pin "2") (pinfunction "2_2") (pintype "bidirectional"))
    )
    (net (code "46") (name "Net-(IC9-SDA)") (class "Default")
      (node (ref "IC9") (pin "E1") (pinfunction "SDA_E1") (pintype "bidirectional"))
      (node (ref "R2") (pin "2") (pinfunction "2_2") (pintype "bidirectional"))
    )
    (net (code "47") (name "Net-(J4-CC1)") (class "Default")
      (node (ref "J4") (pin "A5") (pinfunction "CC1_A5") (pintype "bidirectional"))
      (node (ref "R1_USB") (pin "2") (pinfunction "2_2") (pintype "bidirectional"))
    )
    (net (code "48") (name "Net-(J4-CC2)") (class "Default")
      (node (ref "J4") (pin "B5") (pinfunction "CC2_B5") (pintype "bidirectional"))
      (node (ref "R2_USB") (pin "1") (pinfunction "1_1") (pintype "bidirectional"))
    )
    (net (code "49") (name "Net-(L2-Pad2)") (class "Default")
      (node (ref "L2") (pin "2") (pinfunction "2_2") (pintype "bidirectional"))
      (node (ref "L3") (pin "1") (pinfunction "1_1") (pintype "bidirectional"))
    )
    (net (code "50") (name "Net-(R1_EP_DR-Pad1)") (class "Default")
      (node (ref "R1_EP_DR") (pin "1") (pinfunction "1_1") (pintype "bidirectional"))
      (node (ref "R_TYPE_SEL") (pin "2") (pinfunction "2_2") (pintype "bidirectional"))
      (node (ref "SJ1") (pin "2") (pinfunction "2_2") (pintype "passive"))
    )
    (net (code "51") (name "Net-(U1-ANT)") (class "Default")
      (node (ref "C3") (pin "2") (pinfunction "2_2") (pintype "passive"))
      (node (ref "L1") (pin "1") (pinfunction "1_1") (pintype "bidirectional"))
      (node (ref "U1") (pin "P$H23") (pinfunction "ANT_P$H23") (pintype "bidirectional"))
    )
    (net (code "52") (name "Net-(U1-DCC)") (class "Default")
      (node (ref "L2") (pin "1") (pinfunction "1_1") (pintype "bidirectional"))
      (node (ref "U1") (pin "P$B3") (pinfunction "DCC_P$B3") (pintype "output"))
    )
    (net (code "53") (name "Net-(U1-DEC1)") (class "Default")
      (node (ref "C5") (pin "1") (pinfunction "1_1") (pintype "passive"))
      (node (ref "U1") (pin "P$C1") (pinfunction "DEC1_P$C1") (pintype "power_in"))
    )
    (net (code "54") (name "Net-(U1-DEC2)") (class "Default")
      (node (ref "C13") (pin "2") (pinfunction "2_2") (pintype "passive"))
      (node (ref "U1") (pin "P$A18") (pinfunction "DEC2_P$A18") (pintype "bidirectional"))
    )
    (net (code "55") (name "Net-(U1-DEC3)") (class "Default")
      (node (ref "C11") (pin "2") (pinfunction "2_2") (pintype "passive"))
      (node (ref "U1") (pin "P$D23") (pinfunction "DEC3_P$D23") (pintype "bidirectional"))
    )
    (net (code "56") (name "Net-(U1-DEC3V3)") (class "Default")
      (node (ref "C20") (pin "1") (pinfunction "1_1") (pintype "passive"))
      (node (ref "U1") (pin "P$AC5") (pinfunction "DEC3V3_P$AC5") (pintype "bidirectional"))
    )
    (net (code "57") (name "Net-(U1-DEC4)") (class "Default")
      (node (ref "C10") (pin "1") (pinfunction "1_1") (pintype "passive"))
      (node (ref "C15\\") (pin "1") (pinfunction "1_1") (pintype "passive"))
      (node (ref "C16") (pin "1") (pinfunction "1_1") (pintype "passive"))
      (node (ref "L3") (pin "2") (pinfunction "2_2") (pintype "bidirectional"))
      (node (ref "U1") (pin "P$B5") (pinfunction "DEC4_P$B5") (pintype "power_in"))
      (node (ref "U1") (pin "P$E24") (pinfunction "DEC6_P$E24") (pintype "bidirectional"))
    )
    (net (code "58") (name "Net-(U1-DEC5)") (class "Default")
      (node (ref "C9") (pin "2") (pinfunction "2_2") (pintype "passive"))
      (node (ref "U1") (pin "P$N24") (pinfunction "DEC5_P$N24") (pintype "bidirectional"))
    )
    (net (code "59") (name "Net-(U1-P0.00{slash}XL1)") (class "Default")
      (node (ref "C17") (pin "2") (pinfunction "2_2") (pintype "passive"))
      (node (ref "U1") (pin "P$D2") (pinfunction "P0.00/XL1_P$D2") (pintype "bidirectional"))
      (node (ref "X2") (pin "1") (pinfunction "1_1") (pintype "passive"))
    )
    (net (code "60") (name "Net-(U1-P0.01{slash}XL2)") (class "Default")
      (node (ref "C18") (pin "1") (pinfunction "1_1") (pintype "passive"))
      (node (ref "U1") (pin "P$F2") (pinfunction "P0.01/XL2_P$F2") (pintype "bidirectional"))
      (node (ref "X2") (pin "2") (pinfunction "2_2") (pintype "passive"))
    )
    (net (code "61") (name "Net-(U1-XC1)") (class "Default")
      (node (ref "C1") (pin "1") (pinfunction "1_1") (pintype "passive"))
      (node (ref "U1") (pin "P$B24") (pinfunction "XC1_P$B24") (pintype "input"))
      (node (ref "X1") (pin "1") (pinfunction "1_1") (pintype "passive"))
    )
    (net (code "62") (name "Net-(U1-XC2)") (class "Default")
      (node (ref "C2") (pin "2") (pinfunction "2_2") (pintype "passive"))
      (node (ref "U1") (pin "P$A23") (pinfunction "XC2_P$A23") (pintype "output"))
      (node (ref "X1") (pin "3") (pinfunction "3_3") (pintype "passive"))
    )
    (net (code "63") (name "OUT+") (class "Default")
      (node (ref "IC2") (pin "A3") (pinfunction "OUT+_A3") (pintype "bidirectional"))
      (node (ref "TP_OP") (pin "TP") (pinfunction "TP_TP") (pintype "input"))
    )
    (net (code "64") (name "OUT-") (class "Default")
      (node (ref "IC2") (pin "C3") (pinfunction "OUT-_C3") (pintype "bidirectional"))
      (node (ref "TP_ON") (pin "TP") (pinfunction "TP_TP") (pintype "input"))
    )
    (net (code "65") (name "P0.04") (class "Default")
      (node (ref "U1") (pin "P$J1") (pinfunction "P0.04/AIN2_P$J1") (pintype "bidirectional"))
    )
    (net (code "66") (name "P0.09") (class "Default")
      (node (ref "U1") (pin "P$L24") (pinfunction "P0.09/NFC1_P$L24") (pintype "bidirectional"))
    )
    (net (code "67") (name "P0.13{slash}1.5D") (class "Default")
      (node (ref "C30") (pin "2") (pinfunction "2_2") (pintype "passive"))
      (node (ref "R5") (pin "1") (pinfunction "1_1") (pintype "bidirectional"))
      (node (ref "SW1") (pin "2") (pinfunction "2_2") (pintype "passive"))
    )
    (net (code "68") (name "P0.13{slash}2.6C") (class "Default")
      (node (ref "U1") (pin "P$AD8") (pinfunction "P0.13_P$AD8") (pintype "bidirectional"))
    )
    (net (code "69") (name "P0.14{slash}1.5D") (class "Default")
      (node (ref "C31") (pin "2") (pinfunction "2_2") (pintype "passive"))
      (node (ref "R8") (pin "2") (pinfunction "2_2") (pintype "bidirectional"))
      (node (ref "SW2") (pin "2") (pinfunction "2_2") (pintype "passive"))
    )
    (net (code "70") (name "P0.14{slash}2.7C") (class "Default")
      (node (ref "U1") (pin "P$AC9") (pinfunction "P0.14_P$AC9") (pintype "bidirectional"))
    )
    (net (code "71") (name "P0.19") (class "Default")
      (node (ref "U1") (pin "P$AC15") (pinfunction "P0.19_P$AC15") (pintype "bidirectional"))
    )
    (net (code "72") (name "P0.20") (class "Default")
      (node (ref "U1") (pin "P$AD16") (pinfunction "P0.20_P$AD16") (pintype "bidirectional"))
    )
    (net (code "73") (name "P0.21") (class "Default")
      (node (ref "U1") (pin "P$AC17") (pinfunction "P0.21_P$AC17") (pintype "bidirectional"))
    )
    (net (code "74") (name "P0.22") (class "Default")
      (node (ref "U1") (pin "P$AD18") (pinfunction "P0.22_P$AD18") (pintype "bidirectional"))
    )
    (net (code "75") (name "P0.23") (class "Default")
      (node (ref "U1") (pin "P$AC19") (pinfunction "P0.23_P$AC19") (pintype "bidirectional"))
    )
    (net (code "76") (name "P0.24") (class "Default")
      (node (ref "U1") (pin "P$AD20") (pinfunction "P0.24_P$AD20") (pintype "bidirectional"))
    )
    (net (code "77") (name "P0.25") (class "Default")
      (node (ref "U1") (pin "P$AC21") (pinfunction "P0.25_P$AC21") (pintype "bidirectional"))
    )
    (net (code "78") (name "P0.26") (class "Default")
      (node (ref "U1") (pin "P$G1") (pinfunction "P0.26_P$G1") (pintype "bidirectional"))
    )
    (net (code "79") (name "P0.27") (class "Default")
      (node (ref "U1") (pin "P$H2") (pinfunction "P0.27_P$H2") (pintype "bidirectional"))
    )
    (net (code "80") (name "P0.28") (class "Default")
      (node (ref "U1") (pin "P$B11") (pinfunction "P0.28/AIN4_P$B11") (pintype "bidirectional"))
    )
    (net (code "81") (name "P0.29") (class "Default")
      (node (ref "U1") (pin "P$A10") (pinfunction "P0.29/AIN5_P$A10") (pintype "bidirectional"))
    )
    (net (code "82") (name "P0.30") (class "Default")
      (node (ref "U1") (pin "P$B9") (pinfunction "P0.30/AIN6_P$B9") (pintype "bidirectional"))
    )
    (net (code "83") (name "P0.31") (class "Default")
      (node (ref "U1") (pin "P$A8") (pinfunction "P0.31/AIN7_P$A8") (pintype "bidirectional"))
    )
    (net (code "84") (name "P1.01{slash}1.6C") (class "Default")
      (node (ref "Q1") (pin "1") (pinfunction "G_1") (pintype "bidirectional"))
      (node (ref "R_PWR_EPD") (pin "1") (pinfunction "1_1") (pintype "bidirectional"))
    )
    (net (code "85") (name "P1.01{slash}2.4B") (class "Default")
      (node (ref "U1") (pin "P$Y23") (pinfunction "P1.01_P$Y23") (pintype "bidirectional"))
    )
    (net (code "86") (name "P1.02{slash}1.6C") (class "Default")
      (node (ref "C29") (pin "2") (pinfunction "2_2") (pintype "passive"))
      (node (ref "R7") (pin "1") (pinfunction "1_1") (pintype "bidirectional"))
      (node (ref "SW3") (pin "2") (pinfunction "2_2") (pintype "passive"))
    )
    (net (code "87") (name "P1.02{slash}2.8C") (class "Default")
      (node (ref "U1") (pin "P$W24") (pinfunction "P1.02_P$W24") (pintype "bidirectional"))
    )
    (net (code "88") (name "P1.03") (class "Default")
      (node (ref "U1") (pin "P$V23") (pinfunction "P1.03_P$V23") (pintype "bidirectional"))
    )
    (net (code "89") (name "P1.04") (class "Default")
      (node (ref "U1") (pin "P$U24") (pinfunction "P1.04_P$U24") (pintype "bidirectional"))
    )
    (net (code "90") (name "P1.05") (class "Default")
      (node (ref "U1") (pin "P$T23") (pinfunction "P1.05_P$T23") (pintype "bidirectional"))
    )
    (net (code "91") (name "P1.06") (class "Default")
      (node (ref "U1") (pin "P$R24") (pinfunction "P1.06_P$R24") (pintype "bidirectional"))
    )
    (net (code "92") (name "P1.07") (class "Default")
      (node (ref "U1") (pin "P$P23") (pinfunction "P1.07_P$P23") (pintype "bidirectional"))
    )
    (net (code "93") (name "P1.09") (class "Default")
      (node (ref "U1") (pin "P$R1") (pinfunction "P1.09_P$R1") (pintype "bidirectional"))
    )
    (net (code "94") (name "P1.10") (class "Default")
      (node (ref "U1") (pin "P$A20") (pinfunction "P1.10_P$A20") (pintype "bidirectional"))
    )
    (net (code "95") (name "P1.11") (class "Default")
      (node (ref "U1") (pin "P$B19") (pinfunction "P1.11_P$B19") (pintype "bidirectional"))
    )
    (net (code "96") (name "P1.12") (class "Default")
      (node (ref "U1") (pin "P$B17") (pinfunction "P1.12_P$B17") (pintype "bidirectional"))
    )
    (net (code "97") (name "P1.13") (class "Default")
      (node (ref "U1") (pin "P$A16") (pinfunction "P1.13_P$A16") (pintype "bidirectional"))
    )
    (net (code "98") (name "P1.14") (class "Default")
      (node (ref "U1") (pin "P$B15") (pinfunction "P1.14_P$B15") (pintype "bidirectional"))
    )
    (net (code "99") (name "P1.15") (class "Default")
      (node (ref "U1") (pin "P$A14") (pinfunction "P1.15_P$A14") (pintype "bidirectional"))
    )
    (net (code "100") (name "PMIC_INT") (class "Default")
      (node (ref "IC1") (pin "A1") (pinfunction "~{INT}_A1") (pintype "bidirectional"))
      (node (ref "U1") (pin "P$T2") (pinfunction "P0.11_P$T2") (pintype "bidirectional"))
    )
    (net (code "101") (name "PREVGH") (class "Default")
      (node (ref "D5") (pin "1") (pinfunction "K_1") (pintype "bidirectional"))
      (node (ref "EPD_C9") (pin "1") (pinfunction "1_1") (pintype "passive"))
      (node (ref "J1") (pin "21") (pinfunction "21_21") (pintype "bidirectional"))
    )
    (net (code "102") (name "PREVGL") (class "Default")
      (node (ref "D2") (pin "2") (pinfunction "A_2") (pintype "bidirectional"))
      (node (ref "EPD_C11") (pin "1") (pinfunction "1_1") (pintype "passive"))
      (node (ref "J1") (pin "23") (pinfunction "23_23") (pintype "bidirectional"))
    )
    (net (code "103") (name "RESE") (class "Default")
      (node (ref "J1") (pin "3") (pinfunction "3_3") (pintype "bidirectional"))
      (node (ref "Q3") (pin "2") (pinfunction "S_2") (pintype "bidirectional"))
      (node (ref "R1_EP_DR") (pin "2") (pinfunction "2_2") (pintype "bidirectional"))
    )
    (net (code "104") (name "RESET") (class "Default")
      (node (ref "J2") (pin "6") (pinfunction "6_6") (pintype "bidirectional"))
      (node (ref "TP_RESET") (pin "TP") (pinfunction "TP_TP") (pintype "input"))
      (node (ref "U1") (pin "P$AC13") (pinfunction "P0.18/RESET_P$AC13") (pintype "bidirectional"))
    )
    (net (code "105") (name "SCK{slash}1.5B") (class "Default")
      (node (ref "J1") (pin "13") (pinfunction "13_13") (pintype "bidirectional"))
    )
    (net (code "106") (name "SCK{slash}2.2D") (class "Default")
      (node (ref "U1") (pin "P$A12") (pinfunction "P0.02/AIN0_P$A12") (pintype "bidirectional"))
    )
    (net (code "107") (name "SCL{slash}1.4C") (class "Default")
      (node (ref "IC2") (pin "C1") (pinfunction "SCL_C1") (pintype "bidirectional"))
      (node (ref "U3") (pin "7") (pinfunction "SCL_7") (pintype "input"))
    )
    (net (code "108") (name "SCL{slash}2.4C") (class "Default")
      (node (ref "IC1") (pin "B1") (pinfunction "SCL_B1") (pintype "bidirectional"))
      (node (ref "IC3") (pin "12") (pinfunction "SCX_12") (pintype "bidirectional"))
      (node (ref "R17") (pin "2") (pinfunction "2_2") (pintype "bidirectional"))
      (node (ref "R4") (pin "1") (pinfunction "1_1") (pintype "bidirectional"))
      (node (ref "TP_SCL") (pin "TP") (pinfunction "TP_TP") (pintype "input"))
      (node (ref "U1") (pin "P$M2") (pinfunction "P0.07_P$M2") (pintype "bidirectional"))
    )
    (net (code "109") (name "SDA{slash}1.4C") (class "Default")
      (node (ref "IC2") (pin "B2") (pinfunction "SDA_B2") (pintype "bidirectional"))
      (node (ref "U3") (pin "8") (pinfunction "SDA_8") (pintype "bidirectional"))
    )
    (net (code "110") (name "SDA{slash}2.4C") (class "Default")
      (node (ref "IC1") (pin "C1") (pinfunction "SDA_C1") (pintype "bidirectional"))
      (node (ref "IC3") (pin "2") (pinfunction "SDX_2") (pintype "bidirectional"))
      (node (ref "R18") (pin "2") (pinfunction "2_2") (pintype "bidirectional"))
      (node (ref "R2") (pin "1") (pinfunction "1_1") (pintype "bidirectional"))
      (node (ref "TP_SDA") (pin "TP") (pinfunction "TP_TP") (pintype "input"))
      (node (ref "U1") (pin "P$L1") (pinfunction "P0.06_P$L1") (pintype "bidirectional"))
    )
    (net (code "111") (name "SWDCLK") (class "Default")
      (node (ref "J2") (pin "4") (pinfunction "4_4") (pintype "bidirectional"))
      (node (ref "TP_SWDCLK") (pin "TP") (pinfunction "TP_TP") (pintype "input"))
      (node (ref "U1") (pin "P$AA24") (pinfunction "SWDCLK_P$AA24") (pintype "input"))
    )
    (net (code "112") (name "SWDIO") (class "Default")
      (node (ref "J2") (pin "2") (pinfunction "2_2") (pintype "bidirectional"))
      (node (ref "TP_SWDIO") (pin "TP") (pinfunction "TP_TP") (pintype "input"))
      (node (ref "U1") (pin "P$AC24") (pinfunction "SWDIO_P$AC24") (pintype "bidirectional"))
    )
    (net (code "113") (name "SWO") (class "Default")
      (node (ref "TP_SWO") (pin "TP") (pinfunction "TP_TP") (pintype "input"))
      (node (ref "U1") (pin "P$AD22") (pinfunction "P1.00_P$AD22") (pintype "bidirectional"))
    )
    (net (code "114") (name "VBAT{slash}1.2A") (class "Default")
      (node (ref "C27") (pin "2") (pinfunction "2_2") (pintype "passive"))
      (node (ref "TP_VBAT") (pin "TP") (pinfunction "TP_TP") (pintype "input"))
      (node (ref "U3") (pin "2") (pinfunction "CELL_2") (pintype "power_in"))
      (node (ref "U3") (pin "3") (pinfunction "VDD_3") (pintype "power_in"))
    )
    (net (code "115") (name "VBAT{slash}2.5C") (class "Default")
      (node (ref "C37") (pin "2") (pinfunction "2_2") (pintype "passive"))
      (node (ref "IC1") (pin "C2") (pinfunction "BAT_C2") (pintype "bidirectional"))
    )
    (net (code "116") (name "VBUS{slash}1.5D") (class "Default")
      (node (ref "C42") (pin "1") (pinfunction "1_1") (pintype "passive"))
      (node (ref "C43") (pin "1") (pinfunction "1_1") (pintype "passive"))
      (node (ref "D1") (pin "5") (pinfunction "VBUS_5") (pintype "bidirectional"))
      (node (ref "J4") (pin "A4_B9") (pinfunction "VBUS_A4_B9") (pintype "power_in"))
      (node (ref "J4") (pin "A9_B4") (pinfunction "VBUS_A9_B4") (pintype "power_in"))
    )
    (net (code "117") (name "VBUS{slash}2.6D") (class "Default")
      (node (ref "C21") (pin "1") (pinfunction "1_1") (pintype "passive"))
      (node (ref "C38") (pin "2") (pinfunction "2_2") (pintype "passive"))
      (node (ref "IC1") (pin "A2") (pinfunction "IN_A2") (pintype "bidirectional"))
      (node (ref "U1") (pin "P$AD2") (pinfunction "VBUS_P$AD2") (pintype "power_in"))
    )
    (net (code "118") (name "VREG") (class "Default")
      (node (ref "C23") (pin "2") (pinfunction "2_2") (pintype "passive"))
      (node (ref "C24") (pin "2") (pinfunction "2_2") (pintype "passive"))
      (node (ref "C39") (pin "1") (pinfunction "1_1") (pintype "passive"))
      (node (ref "IC1") (pin "B2") (pinfunction "SYS_B2") (pintype "bidirectional"))
      (node (ref "IC9") (pin "A1") (pinfunction "EN_A1") (pintype "bidirectional"))
      (node (ref "IC9") (pin "A2") (pinfunction "VIN_1_A2") (pintype "bidirectional"))
      (node (ref "IC9") (pin "A3") (pinfunction "VIN_2_A3") (pintype "bidirectional"))
      (node (ref "TP_VREG") (pin "TP") (pinfunction "TP_TP") (pintype "input"))
    )
    (net (code "119") (name "unconnected-(ANT1-NC-Pad2)") (class "Default")
      (node (ref "ANT1") (pin "2") (pinfunction "NC_2") (pintype "no_connect"))
    )
    (net (code "120") (name "unconnected-(IC3-ASCL-Pad11)") (class "Default")
      (node (ref "IC3") (pin "11") (pinfunction "ASCL_11") (pintype "bidirectional"))
    )
    (net (code "121") (name "unconnected-(IC3-ASDA-Pad4)") (class "Default")
      (node (ref "IC3") (pin "4") (pinfunction "ASDA_4") (pintype "bidirectional"))
    )
    (net (code "122") (name "unconnected-(J1-Pad1)") (class "Default")
      (node (ref "J1") (pin "1") (pinfunction "1_1") (pintype "bidirectional"))
    )
    (net (code "123") (name "unconnected-(J1-Pad6)") (class "Default")
      (node (ref "J1") (pin "6") (pinfunction "6_6") (pintype "bidirectional"))
    )
    (net (code "124") (name "unconnected-(J1-Pad7)") (class "Default")
      (node (ref "J1") (pin "7") (pinfunction "7_7") (pintype "bidirectional"))
    )
    (net (code "125") (name "unconnected-(J4-SBU1-PadA8)") (class "Default")
      (node (ref "J4") (pin "A8") (pinfunction "SBU1_A8") (pintype "bidirectional"))
    )
    (net (code "126") (name "unconnected-(J4-SBU2-PadB8)") (class "Default")
      (node (ref "J4") (pin "B8") (pinfunction "SBU2_B8") (pintype "bidirectional"))
    )
    (net (code "127") (name "unconnected-(U1-DCCH-PadP$AB2)") (class "Default")
      (node (ref "U1") (pin "P$AB2") (pinfunction "DCCH_P$AB2") (pintype "bidirectional"))
    )
  )
)
